# pikahome.net
KiCad netlist of a schematic drawn in EAGLE
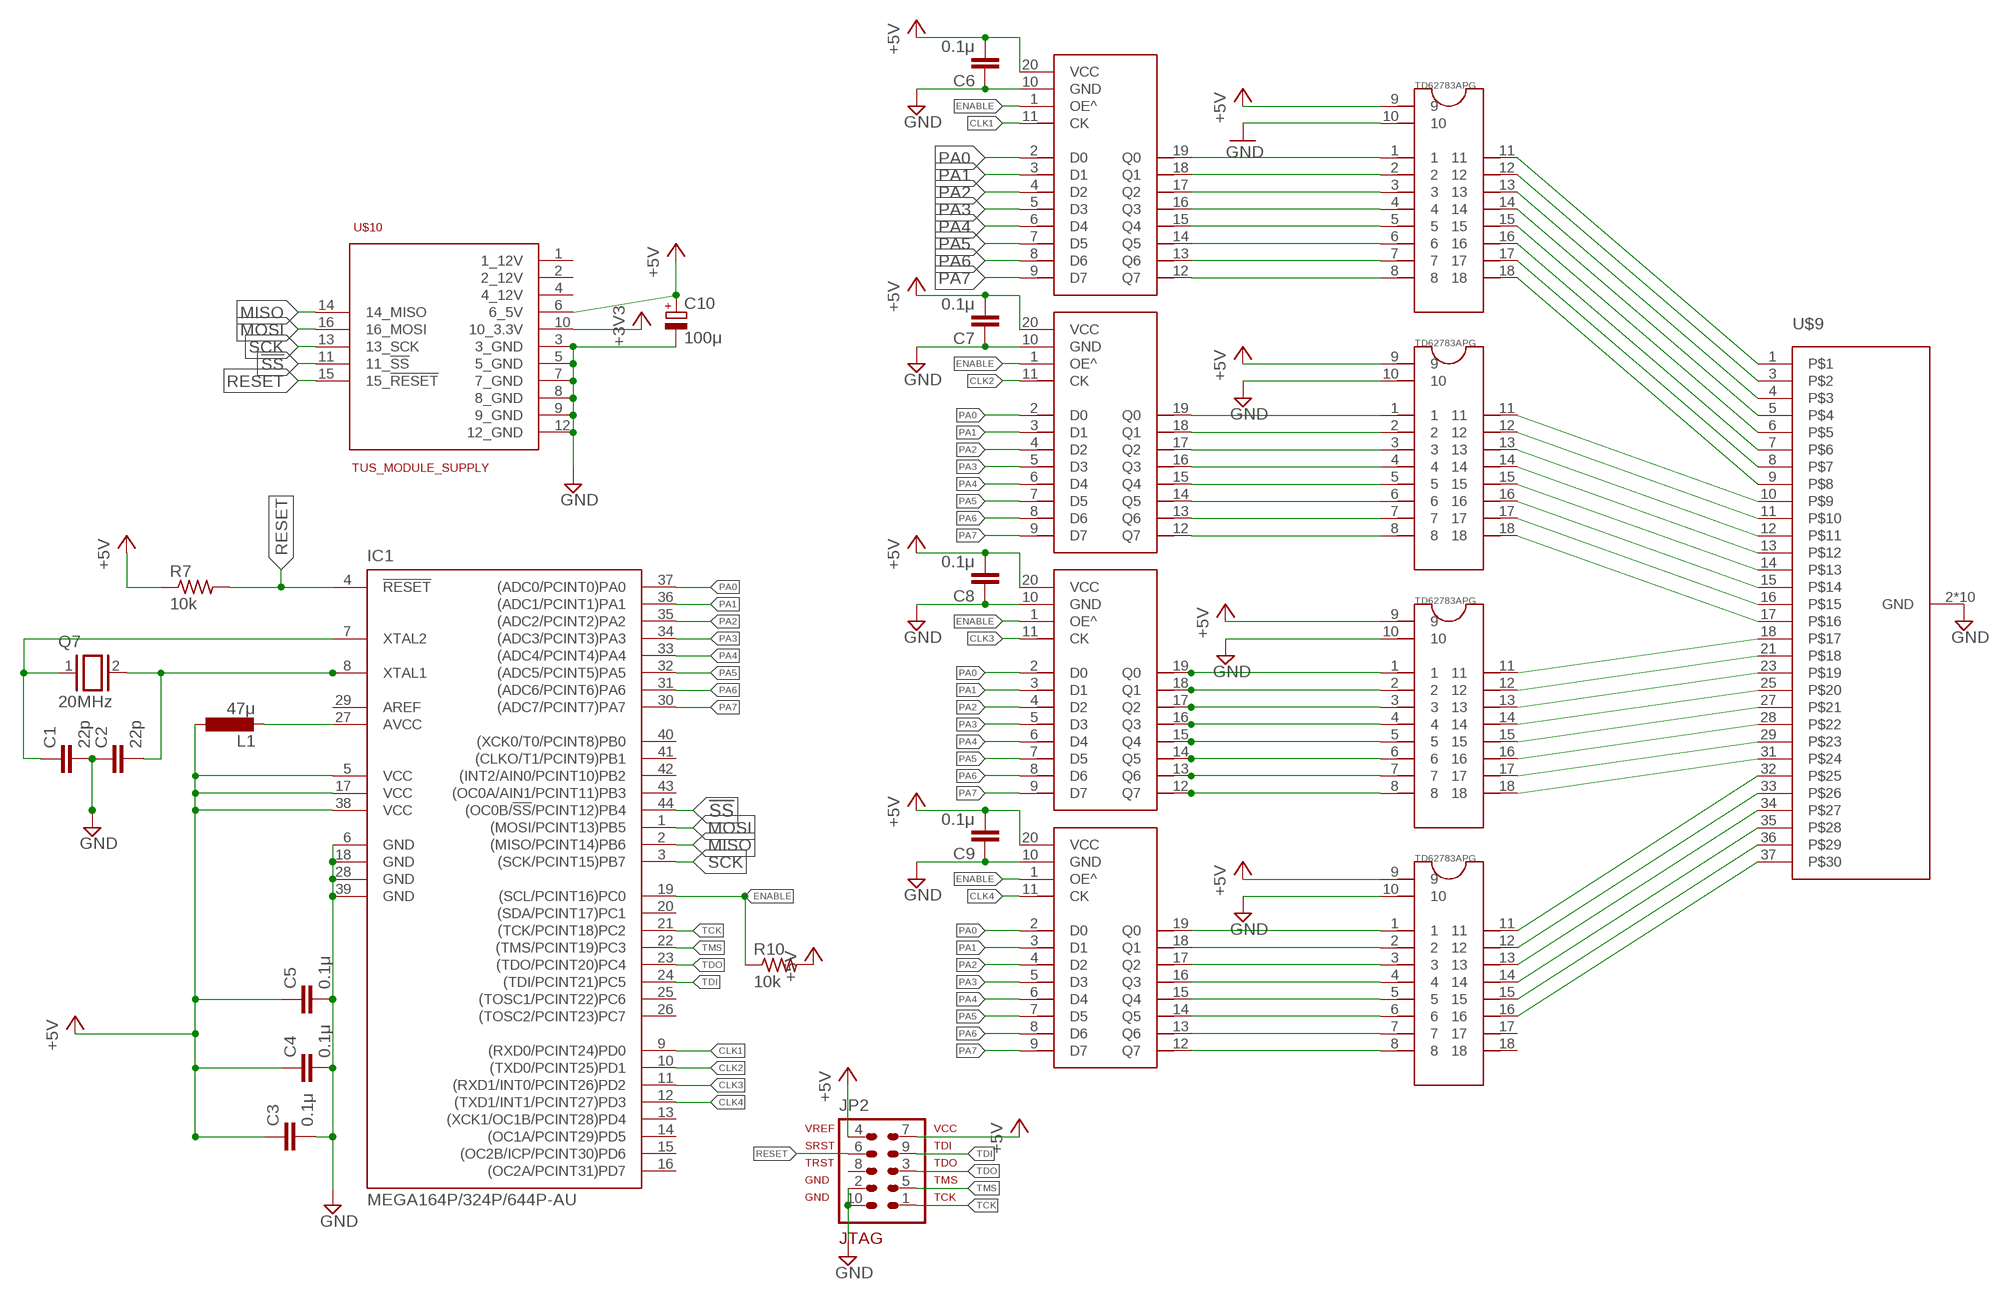
[diagram p0: schematic, sheet 1]

(export (version "E")
  (design (tool "Eeschema 10.0.6"))
  (components
    (comp (ref "C1")
      (value "22p")
      (footprint "eagle-import:C0603")
      (libsource (lib "eagle-import") (part "C-EUC0603"))
    )
    (comp (ref "C2")
      (value "22p")
      (footprint "eagle-import:C0603")
      (libsource (lib "eagle-import") (part "C-EUC0603"))
    )
    (comp (ref "C3")
      (value "0.1μ")
      (footprint "eagle-import:C0603")
      (libsource (lib "eagle-import") (part "C-EUC0603"))
    )
    (comp (ref "C4")
      (value "0.1μ")
      (footprint "eagle-import:C0603")
      (libsource (lib "eagle-import") (part "C-EUC0603"))
    )
    (comp (ref "C5")
      (value "0.1μ")
      (footprint "eagle-import:C0603")
      (libsource (lib "eagle-import") (part "C-EUC0603"))
    )
    (comp (ref "C6")
      (value "0.1μ")
      (footprint "eagle-import:C0603")
      (libsource (lib "eagle-import") (part "C-EUC0603"))
    )
    (comp (ref "C7")
      (value "0.1μ")
      (footprint "eagle-import:C0603")
      (libsource (lib "eagle-import") (part "C-EUC0603"))
    )
    (comp (ref "C8")
      (value "0.1μ")
      (footprint "eagle-import:C0603")
      (libsource (lib "eagle-import") (part "C-EUC0603"))
    )
    (comp (ref "C9")
      (value "0.1μ")
      (footprint "eagle-import:C0603")
      (libsource (lib "eagle-import") (part "C-EUC0603"))
    )
    (comp (ref "C10")
      (value "100μ")
      (footprint "eagle-import:TT2D5")
      (libsource (lib "eagle-import") (part "CPOL-EUTT2D5"))
    )
    (comp (ref "IC1")
      (value "MEGA164P/324P/644P-AU")
      (footprint "eagle-import:TQFP44")
      (libsource (lib "eagle-import") (part "MEGA164P/324P/644P-AU"))
    )
    (comp (ref "JP2")
      (value "AVR-JTAG-10")
      (footprint "eagle-import:AVR-JTAG-10")
      (libsource (lib "eagle-import") (part "AVR-JTAG-10"))
    )
    (comp (ref "L1")
      (value "47μ")
      (footprint "eagle-import:L3216C")
      (libsource (lib "eagle-import") (part "L-EUL3216C"))
    )
    (comp (ref "Q7")
      (value "20MHz")
      (footprint "eagle-import:QS")
      (libsource (lib "eagle-import") (part "XTAL/S"))
    )
    (comp (ref "R7")
      (value "10k")
      (footprint "eagle-import:R0603")
      (libsource (lib "eagle-import") (part "R-US_R0603"))
    )
    (comp (ref "R10")
      (value "10k")
      (footprint "eagle-import:R0603")
      (libsource (lib "eagle-import") (part "R-US_R0603"))
    )
    (comp (ref "U$1")
      (value "TD62783APG")
      (footprint "eagle-import:DIL18")
      (libsource (lib "eagle-import") (part "TD62783APG"))
    )
    (comp (ref "U$2")
      (value "TD62783APG")
      (footprint "eagle-import:DIL18")
      (libsource (lib "eagle-import") (part "TD62783APG"))
    )
    (comp (ref "U$3")
      (value "74VHC574F")
      (footprint "eagle-import:SO20W")
      (libsource (lib "eagle-import") (part "74VHC574F"))
    )
    (comp (ref "U$4")
      (value "74VHC574F")
      (footprint "eagle-import:SO20W")
      (libsource (lib "eagle-import") (part "74VHC574F"))
    )
    (comp (ref "U$5")
      (value "74VHC574F")
      (footprint "eagle-import:SO20W")
      (libsource (lib "eagle-import") (part "74VHC574F"))
    )
    (comp (ref "U$6")
      (value "TD62783APG")
      (footprint "eagle-import:DIL18")
      (libsource (lib "eagle-import") (part "TD62783APG"))
    )
    (comp (ref "U$7")
      (value "74VHC574F")
      (footprint "eagle-import:SO20W")
      (libsource (lib "eagle-import") (part "74VHC574F"))
    )
    (comp (ref "U$8")
      (value "TD62783APG")
      (footprint "eagle-import:DIL18")
      (libsource (lib "eagle-import") (part "TD62783APG"))
    )
    (comp (ref "U$9")
      (value "LED_40")
      (footprint "eagle-import:PAK100_2500-40")
      (libsource (lib "eagle-import") (part "LED_40"))
    )
    (comp (ref "U$10")
      (value "TUS_MODULE_SUPPLY")
      (footprint "eagle-import:2X08")
      (libsource (lib "eagle-import") (part "TUS_MODULE_SUPPLY"))
    )
  )
  (nets
    (net (code "1") (name "+3V3") (class "Default")
      (node (ref "U$10") (pin "10") (pinfunction "10_3.3V_10") (pintype "bidirectional"))
    )
    (net (code "2") (name "+5V") (class "Default")
      (node (ref "C10") (pin "+") (pinfunction "+_+") (pintype "passive"))
      (node (ref "C3") (pin "1") (pinfunction "1_1") (pintype "passive"))
      (node (ref "C4") (pin "1") (pinfunction "1_1") (pintype "passive"))
      (node (ref "C5") (pin "1") (pinfunction "1_1") (pintype "passive"))
      (node (ref "C6") (pin "2") (pinfunction "2_2") (pintype "passive"))
      (node (ref "C7") (pin "2") (pinfunction "2_2") (pintype "passive"))
      (node (ref "C8") (pin "2") (pinfunction "2_2") (pintype "passive"))
      (node (ref "C9") (pin "2") (pinfunction "2_2") (pintype "passive"))
      (node (ref "IC1") (pin "17") (pinfunction "VCC_17") (pintype "power_in"))
      (node (ref "IC1") (pin "38") (pinfunction "VCC_38") (pintype "power_in"))
      (node (ref "IC1") (pin "5") (pinfunction "VCC_5") (pintype "power_in"))
      (node (ref "JP2") (pin "4") (pinfunction "4_4") (pintype "passive"))
      (node (ref "JP2") (pin "7") (pinfunction "7_7") (pintype "passive"))
      (node (ref "L1") (pin "1") (pinfunction "1_1") (pintype "passive"))
      (node (ref "R10") (pin "2") (pinfunction "2_2") (pintype "passive"))
      (node (ref "R7") (pin "1") (pinfunction "1_1") (pintype "passive"))
      (node (ref "U$1") (pin "9") (pinfunction "9_9") (pintype "power_in"))
      (node (ref "U$10") (pin "6") (pinfunction "6_5V_6") (pintype "bidirectional"))
      (node (ref "U$2") (pin "9") (pinfunction "9_9") (pintype "power_in"))
      (node (ref "U$3") (pin "20") (pinfunction "VCC_20") (pintype "bidirectional"))
      (node (ref "U$4") (pin "20") (pinfunction "VCC_20") (pintype "bidirectional"))
      (node (ref "U$5") (pin "20") (pinfunction "VCC_20") (pintype "bidirectional"))
      (node (ref "U$6") (pin "9") (pinfunction "9_9") (pintype "power_in"))
      (node (ref "U$7") (pin "20") (pinfunction "VCC_20") (pintype "bidirectional"))
      (node (ref "U$8") (pin "9") (pinfunction "9_9") (pintype "power_in"))
    )
    (net (code "3") (name "/AREF") (class "Default")
      (node (ref "IC1") (pin "29") (pinfunction "AREF_29") (pintype "power_in"))
    )
    (net (code "4") (name "/~{SS}") (class "Default")
      (node (ref "IC1") (pin "44") (pinfunction "(OC0B/~{SS}/PCINT12)PB4_44") (pintype "bidirectional"))
      (node (ref "U$10") (pin "11") (pinfunction "11_~{SS}_11") (pintype "bidirectional"))
    )
    (net (code "5") (name "CLK1") (class "Default")
      (node (ref "IC1") (pin "9") (pinfunction "(RXD0/PCINT24)PD0_9") (pintype "bidirectional"))
      (node (ref "U$3") (pin "11") (pinfunction "CK_11") (pintype "bidirectional"))
    )
    (net (code "6") (name "CLK2") (class "Default")
      (node (ref "IC1") (pin "10") (pinfunction "(TXD0/PCINT25)PD1_10") (pintype "bidirectional"))
      (node (ref "U$4") (pin "11") (pinfunction "CK_11") (pintype "bidirectional"))
    )
    (net (code "7") (name "CLK3") (class "Default")
      (node (ref "IC1") (pin "11") (pinfunction "(RXD1/INT0/PCINT26)PD2_11") (pintype "bidirectional"))
      (node (ref "U$5") (pin "11") (pinfunction "CK_11") (pintype "bidirectional"))
    )
    (net (code "8") (name "CLK4") (class "Default")
      (node (ref "IC1") (pin "12") (pinfunction "(TXD1/INT1/PCINT27)PD3_12") (pintype "bidirectional"))
      (node (ref "U$7") (pin "11") (pinfunction "CK_11") (pintype "bidirectional"))
    )
    (net (code "9") (name "ENABLE") (class "Default")
      (node (ref "IC1") (pin "19") (pinfunction "(SCL/PCINT16)PC0_19") (pintype "bidirectional"))
      (node (ref "R10") (pin "1") (pinfunction "1_1") (pintype "passive"))
      (node (ref "U$3") (pin "1") (pinfunction "OE^_1") (pintype "bidirectional"))
      (node (ref "U$4") (pin "1") (pinfunction "OE^_1") (pintype "bidirectional"))
      (node (ref "U$5") (pin "1") (pinfunction "OE^_1") (pintype "bidirectional"))
      (node (ref "U$7") (pin "1") (pinfunction "OE^_1") (pintype "bidirectional"))
    )
    (net (code "10") (name "GND") (class "Default")
      (node (ref "C1") (pin "2") (pinfunction "2_2") (pintype "passive"))
      (node (ref "C10") (pin "-") (pinfunction "-_-") (pintype "passive"))
      (node (ref "C2") (pin "1") (pinfunction "1_1") (pintype "passive"))
      (node (ref "C3") (pin "2") (pinfunction "2_2") (pintype "passive"))
      (node (ref "C4") (pin "2") (pinfunction "2_2") (pintype "passive"))
      (node (ref "C5") (pin "2") (pinfunction "2_2") (pintype "passive"))
      (node (ref "C6") (pin "1") (pinfunction "1_1") (pintype "passive"))
      (node (ref "C7") (pin "1") (pinfunction "1_1") (pintype "passive"))
      (node (ref "C8") (pin "1") (pinfunction "1_1") (pintype "passive"))
      (node (ref "C9") (pin "1") (pinfunction "1_1") (pintype "passive"))
      (node (ref "IC1") (pin "18") (pinfunction "GND_18") (pintype "power_in"))
      (node (ref "IC1") (pin "28") (pinfunction "GND_28") (pintype "power_in"))
      (node (ref "IC1") (pin "39") (pinfunction "GND_39") (pintype "power_in"))
      (node (ref "IC1") (pin "6") (pinfunction "GND_6") (pintype "power_in"))
      (node (ref "JP2") (pin "10") (pinfunction "10_10") (pintype "passive"))
      (node (ref "JP2") (pin "2") (pinfunction "2_2") (pintype "passive"))
      (node (ref "U$1") (pin "10") (pinfunction "10_10") (pintype "power_in"))
      (node (ref "U$10") (pin "12") (pinfunction "12_GND_12") (pintype "bidirectional"))
      (node (ref "U$10") (pin "3") (pinfunction "3_GND_3") (pintype "bidirectional"))
      (node (ref "U$10") (pin "5") (pinfunction "5_GND_5") (pintype "bidirectional"))
      (node (ref "U$10") (pin "7") (pinfunction "7_GND_7") (pintype "bidirectional"))
      (node (ref "U$10") (pin "8") (pinfunction "8_GND_8") (pintype "bidirectional"))
      (node (ref "U$10") (pin "9") (pinfunction "9_GND_9") (pintype "bidirectional"))
      (node (ref "U$2") (pin "10") (pinfunction "10_10") (pintype "power_in"))
      (node (ref "U$3") (pin "10") (pinfunction "GND_10") (pintype "bidirectional"))
      (node (ref "U$4") (pin "10") (pinfunction "GND_10") (pintype "bidirectional"))
      (node (ref "U$5") (pin "10") (pinfunction "GND_10") (pintype "bidirectional"))
      (node (ref "U$6") (pin "10") (pinfunction "10_10") (pintype "power_in"))
      (node (ref "U$7") (pin "10") (pinfunction "GND_10") (pintype "bidirectional"))
      (node (ref "U$8") (pin "10") (pinfunction "10_10") (pintype "power_in"))
      (node (ref "U$9") (pin "19") (pinfunction "GND_19") (pintype "bidirectional"))
      (node (ref "U$9") (pin "2") (pinfunction "GND_2") (pintype "bidirectional"))
      (node (ref "U$9") (pin "20") (pinfunction "GND_20") (pintype "bidirectional"))
      (node (ref "U$9") (pin "22") (pinfunction "GND_22") (pintype "bidirectional"))
      (node (ref "U$9") (pin "24") (pinfunction "GND_24") (pintype "bidirectional"))
      (node (ref "U$9") (pin "26") (pinfunction "GND_26") (pintype "bidirectional"))
      (node (ref "U$9") (pin "30") (pinfunction "GND_30") (pintype "bidirectional"))
      (node (ref "U$9") (pin "38") (pinfunction "GND_38") (pintype "bidirectional"))
      (node (ref "U$9") (pin "39") (pinfunction "GND_39") (pintype "bidirectional"))
      (node (ref "U$9") (pin "40") (pinfunction "GND_40") (pintype "bidirectional"))
    )
    (net (code "11") (name "MISO") (class "Default")
      (node (ref "IC1") (pin "2") (pinfunction "(MISO/PCINT14)PB6_2") (pintype "bidirectional"))
      (node (ref "U$10") (pin "14") (pinfunction "14_MISO_14") (pintype "bidirectional"))
    )
    (net (code "12") (name "MOSI") (class "Default")
      (node (ref "IC1") (pin "1") (pinfunction "(MOSI/PCINT13)PB5_1") (pintype "bidirectional"))
      (node (ref "U$10") (pin "16") (pinfunction "16_MOSI_16") (pintype "bidirectional"))
    )
    (net (code "13") (name "Net-(IC1-AVCC)") (class "Default")
      (node (ref "IC1") (pin "27") (pinfunction "AVCC_27") (pintype "power_in"))
      (node (ref "L1") (pin "2") (pinfunction "2_2") (pintype "passive"))
    )
    (net (code "14") (name "Net-(IC1-XTAL1)") (class "Default")
      (node (ref "C2") (pin "2") (pinfunction "2_2") (pintype "passive"))
      (node (ref "IC1") (pin "8") (pinfunction "XTAL1_8") (pintype "input"))
      (node (ref "Q7") (pin "2") (pinfunction "2_2") (pintype "passive"))
    )
    (net (code "15") (name "Net-(IC1-XTAL2)") (class "Default")
      (node (ref "C1") (pin "1") (pinfunction "1_1") (pintype "passive"))
      (node (ref "IC1") (pin "7") (pinfunction "XTAL2_7") (pintype "output"))
      (node (ref "Q7") (pin "1") (pinfunction "1_1") (pintype "passive"))
    )
    (net (code "16") (name "Net-(U$3-Q0)") (class "Default")
      (node (ref "U$1") (pin "1") (pinfunction "1_1") (pintype "input"))
      (node (ref "U$3") (pin "19") (pinfunction "Q0_19") (pintype "bidirectional"))
    )
    (net (code "17") (name "Net-(U$3-Q1)") (class "Default")
      (node (ref "U$1") (pin "2") (pinfunction "2_2") (pintype "input"))
      (node (ref "U$3") (pin "18") (pinfunction "Q1_18") (pintype "bidirectional"))
    )
    (net (code "18") (name "Net-(U$3-Q2)") (class "Default")
      (node (ref "U$1") (pin "3") (pinfunction "3_3") (pintype "input"))
      (node (ref "U$3") (pin "17") (pinfunction "Q2_17") (pintype "bidirectional"))
    )
    (net (code "19") (name "Net-(U$3-Q3)") (class "Default")
      (node (ref "U$1") (pin "4") (pinfunction "4_4") (pintype "input"))
      (node (ref "U$3") (pin "16") (pinfunction "Q3_16") (pintype "bidirectional"))
    )
    (net (code "20") (name "Net-(U$3-Q4)") (class "Default")
      (node (ref "U$1") (pin "5") (pinfunction "5_5") (pintype "input"))
      (node (ref "U$3") (pin "15") (pinfunction "Q4_15") (pintype "bidirectional"))
    )
    (net (code "21") (name "Net-(U$3-Q5)") (class "Default")
      (node (ref "U$1") (pin "6") (pinfunction "6_6") (pintype "input"))
      (node (ref "U$3") (pin "14") (pinfunction "Q5_14") (pintype "bidirectional"))
    )
    (net (code "22") (name "Net-(U$3-Q6)") (class "Default")
      (node (ref "U$1") (pin "7") (pinfunction "7_7") (pintype "input"))
      (node (ref "U$3") (pin "13") (pinfunction "Q6_13") (pintype "bidirectional"))
    )
    (net (code "23") (name "Net-(U$3-Q7)") (class "Default")
      (node (ref "U$1") (pin "8") (pinfunction "8_8") (pintype "input"))
      (node (ref "U$3") (pin "12") (pinfunction "Q7_12") (pintype "bidirectional"))
    )
    (net (code "24") (name "Net-(U$4-Q0)") (class "Default")
      (node (ref "U$2") (pin "1") (pinfunction "1_1") (pintype "input"))
      (node (ref "U$4") (pin "19") (pinfunction "Q0_19") (pintype "bidirectional"))
    )
    (net (code "25") (name "Net-(U$4-Q1)") (class "Default")
      (node (ref "U$2") (pin "2") (pinfunction "2_2") (pintype "input"))
      (node (ref "U$4") (pin "18") (pinfunction "Q1_18") (pintype "bidirectional"))
    )
    (net (code "26") (name "Net-(U$4-Q2)") (class "Default")
      (node (ref "U$2") (pin "3") (pinfunction "3_3") (pintype "input"))
      (node (ref "U$4") (pin "17") (pinfunction "Q2_17") (pintype "bidirectional"))
    )
    (net (code "27") (name "Net-(U$4-Q3)") (class "Default")
      (node (ref "U$2") (pin "4") (pinfunction "4_4") (pintype "input"))
      (node (ref "U$4") (pin "16") (pinfunction "Q3_16") (pintype "bidirectional"))
    )
    (net (code "28") (name "Net-(U$4-Q4)") (class "Default")
      (node (ref "U$2") (pin "5") (pinfunction "5_5") (pintype "input"))
      (node (ref "U$4") (pin "15") (pinfunction "Q4_15") (pintype "bidirectional"))
    )
    (net (code "29") (name "Net-(U$4-Q5)") (class "Default")
      (node (ref "U$2") (pin "6") (pinfunction "6_6") (pintype "input"))
      (node (ref "U$4") (pin "14") (pinfunction "Q5_14") (pintype "bidirectional"))
    )
    (net (code "30") (name "Net-(U$4-Q6)") (class "Default")
      (node (ref "U$2") (pin "7") (pinfunction "7_7") (pintype "input"))
      (node (ref "U$4") (pin "13") (pinfunction "Q6_13") (pintype "bidirectional"))
    )
    (net (code "31") (name "Net-(U$4-Q7)") (class "Default")
      (node (ref "U$2") (pin "8") (pinfunction "8_8") (pintype "input"))
      (node (ref "U$4") (pin "12") (pinfunction "Q7_12") (pintype "bidirectional"))
    )
    (net (code "32") (name "Net-(U$5-Q0)") (class "Default")
      (node (ref "U$5") (pin "19") (pinfunction "Q0_19") (pintype "bidirectional"))
      (node (ref "U$6") (pin "1") (pinfunction "1_1") (pintype "input"))
    )
    (net (code "33") (name "Net-(U$5-Q1)") (class "Default")
      (node (ref "U$5") (pin "18") (pinfunction "Q1_18") (pintype "bidirectional"))
      (node (ref "U$6") (pin "2") (pinfunction "2_2") (pintype "input"))
    )
    (net (code "34") (name "Net-(U$5-Q2)") (class "Default")
      (node (ref "U$5") (pin "17") (pinfunction "Q2_17") (pintype "bidirectional"))
      (node (ref "U$6") (pin "3") (pinfunction "3_3") (pintype "input"))
    )
    (net (code "35") (name "Net-(U$5-Q3)") (class "Default")
      (node (ref "U$5") (pin "16") (pinfunction "Q3_16") (pintype "bidirectional"))
      (node (ref "U$6") (pin "4") (pinfunction "4_4") (pintype "input"))
    )
    (net (code "36") (name "Net-(U$5-Q4)") (class "Default")
      (node (ref "U$5") (pin "15") (pinfunction "Q4_15") (pintype "bidirectional"))
      (node (ref "U$6") (pin "5") (pinfunction "5_5") (pintype "input"))
    )
    (net (code "37") (name "Net-(U$5-Q5)") (class "Default")
      (node (ref "U$5") (pin "14") (pinfunction "Q5_14") (pintype "bidirectional"))
      (node (ref "U$6") (pin "6") (pinfunction "6_6") (pintype "input"))
    )
    (net (code "38") (name "Net-(U$5-Q6)") (class "Default")
      (node (ref "U$5") (pin "13") (pinfunction "Q6_13") (pintype "bidirectional"))
      (node (ref "U$6") (pin "7") (pinfunction "7_7") (pintype "input"))
    )
    (net (code "39") (name "Net-(U$5-Q7)") (class "Default")
      (node (ref "U$5") (pin "12") (pinfunction "Q7_12") (pintype "bidirectional"))
      (node (ref "U$6") (pin "8") (pinfunction "8_8") (pintype "input"))
    )
    (net (code "40") (name "Net-(U$7-Q0)") (class "Default")
      (node (ref "U$7") (pin "19") (pinfunction "Q0_19") (pintype "bidirectional"))
      (node (ref "U$8") (pin "1") (pinfunction "1_1") (pintype "input"))
    )
    (net (code "41") (name "Net-(U$7-Q1)") (class "Default")
      (node (ref "U$7") (pin "18") (pinfunction "Q1_18") (pintype "bidirectional"))
      (node (ref "U$8") (pin "2") (pinfunction "2_2") (pintype "input"))
    )
    (net (code "42") (name "Net-(U$7-Q2)") (class "Default")
      (node (ref "U$7") (pin "17") (pinfunction "Q2_17") (pintype "bidirectional"))
      (node (ref "U$8") (pin "3") (pinfunction "3_3") (pintype "input"))
    )
    (net (code "43") (name "Net-(U$7-Q3)") (class "Default")
      (node (ref "U$7") (pin "16") (pinfunction "Q3_16") (pintype "bidirectional"))
      (node (ref "U$8") (pin "4") (pinfunction "4_4") (pintype "input"))
    )
    (net (code "44") (name "Net-(U$7-Q4)") (class "Default")
      (node (ref "U$7") (pin "15") (pinfunction "Q4_15") (pintype "bidirectional"))
      (node (ref "U$8") (pin "5") (pinfunction "5_5") (pintype "input"))
    )
    (net (code "45") (name "Net-(U$7-Q5)") (class "Default")
      (node (ref "U$7") (pin "14") (pinfunction "Q5_14") (pintype "bidirectional"))
      (node (ref "U$8") (pin "6") (pinfunction "6_6") (pintype "input"))
    )
    (net (code "46") (name "Net-(U$7-Q6)") (class "Default")
      (node (ref "U$7") (pin "13") (pinfunction "Q6_13") (pintype "bidirectional"))
      (node (ref "U$8") (pin "7") (pinfunction "7_7") (pintype "input"))
    )
    (net (code "47") (name "Net-(U$7-Q7)") (class "Default")
      (node (ref "U$7") (pin "12") (pinfunction "Q7_12") (pintype "bidirectional"))
      (node (ref "U$8") (pin "8") (pinfunction "8_8") (pintype "input"))
    )
    (net (code "48") (name "Net-(U$9-P$1)") (class "Default")
      (node (ref "U$1") (pin "11") (pinfunction "11_11") (pintype "output"))
      (node (ref "U$9") (pin "1") (pinfunction "P$1_1") (pintype "bidirectional"))
    )
    (net (code "49") (name "Net-(U$9-P$2)") (class "Default")
      (node (ref "U$1") (pin "12") (pinfunction "12_12") (pintype "output"))
      (node (ref "U$9") (pin "3") (pinfunction "P$2_3") (pintype "bidirectional"))
    )
    (net (code "50") (name "Net-(U$9-P$3)") (class "Default")
      (node (ref "U$1") (pin "13") (pinfunction "13_13") (pintype "output"))
      (node (ref "U$9") (pin "4") (pinfunction "P$3_4") (pintype "bidirectional"))
    )
    (net (code "51") (name "Net-(U$9-P$4)") (class "Default")
      (node (ref "U$1") (pin "14") (pinfunction "14_14") (pintype "output"))
      (node (ref "U$9") (pin "5") (pinfunction "P$4_5") (pintype "bidirectional"))
    )
    (net (code "52") (name "Net-(U$9-P$5)") (class "Default")
      (node (ref "U$1") (pin "15") (pinfunction "15_15") (pintype "output"))
      (node (ref "U$9") (pin "6") (pinfunction "P$5_6") (pintype "bidirectional"))
    )
    (net (code "53") (name "Net-(U$9-P$6)") (class "Default")
      (node (ref "U$1") (pin "16") (pinfunction "16_16") (pintype "output"))
      (node (ref "U$9") (pin "7") (pinfunction "P$6_7") (pintype "bidirectional"))
    )
    (net (code "54") (name "Net-(U$9-P$7)") (class "Default")
      (node (ref "U$1") (pin "17") (pinfunction "17_17") (pintype "output"))
      (node (ref "U$9") (pin "8") (pinfunction "P$7_8") (pintype "bidirectional"))
    )
    (net (code "55") (name "Net-(U$9-P$8)") (class "Default")
      (node (ref "U$1") (pin "18") (pinfunction "18_18") (pintype "output"))
      (node (ref "U$9") (pin "9") (pinfunction "P$8_9") (pintype "bidirectional"))
    )
    (net (code "56") (name "Net-(U$9-P$9)") (class "Default")
      (node (ref "U$2") (pin "11") (pinfunction "11_11") (pintype "output"))
      (node (ref "U$9") (pin "10") (pinfunction "P$9_10") (pintype "bidirectional"))
    )
    (net (code "57") (name "Net-(U$9-P$10)") (class "Default")
      (node (ref "U$2") (pin "12") (pinfunction "12_12") (pintype "output"))
      (node (ref "U$9") (pin "11") (pinfunction "P$10_11") (pintype "bidirectional"))
    )
    (net (code "58") (name "Net-(U$9-P$11)") (class "Default")
      (node (ref "U$2") (pin "13") (pinfunction "13_13") (pintype "output"))
      (node (ref "U$9") (pin "12") (pinfunction "P$11_12") (pintype "bidirectional"))
    )
    (net (code "59") (name "Net-(U$9-P$12)") (class "Default")
      (node (ref "U$2") (pin "14") (pinfunction "14_14") (pintype "output"))
      (node (ref "U$9") (pin "13") (pinfunction "P$12_13") (pintype "bidirectional"))
    )
    (net (code "60") (name "Net-(U$9-P$13)") (class "Default")
      (node (ref "U$2") (pin "15") (pinfunction "15_15") (pintype "output"))
      (node (ref "U$9") (pin "14") (pinfunction "P$13_14") (pintype "bidirectional"))
    )
    (net (code "61") (name "Net-(U$9-P$14)") (class "Default")
      (node (ref "U$2") (pin "16") (pinfunction "16_16") (pintype "output"))
      (node (ref "U$9") (pin "15") (pinfunction "P$14_15") (pintype "bidirectional"))
    )
    (net (code "62") (name "Net-(U$9-P$15)") (class "Default")
      (node (ref "U$2") (pin "17") (pinfunction "17_17") (pintype "output"))
      (node (ref "U$9") (pin "16") (pinfunction "P$15_16") (pintype "bidirectional"))
    )
    (net (code "63") (name "Net-(U$9-P$16)") (class "Default")
      (node (ref "U$2") (pin "18") (pinfunction "18_18") (pintype "output"))
      (node (ref "U$9") (pin "17") (pinfunction "P$16_17") (pintype "bidirectional"))
    )
    (net (code "64") (name "Net-(U$9-P$17)") (class "Default")
      (node (ref "U$6") (pin "11") (pinfunction "11_11") (pintype "output"))
      (node (ref "U$9") (pin "18") (pinfunction "P$17_18") (pintype "bidirectional"))
    )
    (net (code "65") (name "Net-(U$9-P$18)") (class "Default")
      (node (ref "U$6") (pin "12") (pinfunction "12_12") (pintype "output"))
      (node (ref "U$9") (pin "21") (pinfunction "P$18_21") (pintype "bidirectional"))
    )
    (net (code "66") (name "Net-(U$9-P$19)") (class "Default")
      (node (ref "U$6") (pin "13") (pinfunction "13_13") (pintype "output"))
      (node (ref "U$9") (pin "23") (pinfunction "P$19_23") (pintype "bidirectional"))
    )
    (net (code "67") (name "Net-(U$9-P$20)") (class "Default")
      (node (ref "U$6") (pin "14") (pinfunction "14_14") (pintype "output"))
      (node (ref "U$9") (pin "25") (pinfunction "P$20_25") (pintype "bidirectional"))
    )
    (net (code "68") (name "Net-(U$9-P$21)") (class "Default")
      (node (ref "U$6") (pin "15") (pinfunction "15_15") (pintype "output"))
      (node (ref "U$9") (pin "27") (pinfunction "P$21_27") (pintype "bidirectional"))
    )
    (net (code "69") (name "Net-(U$9-P$22)") (class "Default")
      (node (ref "U$6") (pin "16") (pinfunction "16_16") (pintype "output"))
      (node (ref "U$9") (pin "28") (pinfunction "P$22_28") (pintype "bidirectional"))
    )
    (net (code "70") (name "Net-(U$9-P$23)") (class "Default")
      (node (ref "U$6") (pin "17") (pinfunction "17_17") (pintype "output"))
      (node (ref "U$9") (pin "29") (pinfunction "P$23_29") (pintype "bidirectional"))
    )
    (net (code "71") (name "Net-(U$9-P$24)") (class "Default")
      (node (ref "U$6") (pin "18") (pinfunction "18_18") (pintype "output"))
      (node (ref "U$9") (pin "31") (pinfunction "P$24_31") (pintype "bidirectional"))
    )
    (net (code "72") (name "Net-(U$9-P$25)") (class "Default")
      (node (ref "U$8") (pin "11") (pinfunction "11_11") (pintype "output"))
      (node (ref "U$9") (pin "32") (pinfunction "P$25_32") (pintype "bidirectional"))
    )
    (net (code "73") (name "Net-(U$9-P$26)") (class "Default")
      (node (ref "U$8") (pin "12") (pinfunction "12_12") (pintype "output"))
      (node (ref "U$9") (pin "33") (pinfunction "P$26_33") (pintype "bidirectional"))
    )
    (net (code "74") (name "Net-(U$9-P$27)") (class "Default")
      (node (ref "U$8") (pin "13") (pinfunction "13_13") (pintype "output"))
      (node (ref "U$9") (pin "34") (pinfunction "P$27_34") (pintype "bidirectional"))
    )
    (net (code "75") (name "Net-(U$9-P$28)") (class "Default")
      (node (ref "U$8") (pin "14") (pinfunction "14_14") (pintype "output"))
      (node (ref "U$9") (pin "35") (pinfunction "P$28_35") (pintype "bidirectional"))
    )
    (net (code "76") (name "Net-(U$9-P$29)") (class "Default")
      (node (ref "U$8") (pin "15") (pinfunction "15_15") (pintype "output"))
      (node (ref "U$9") (pin "36") (pinfunction "P$29_36") (pintype "bidirectional"))
    )
    (net (code "77") (name "Net-(U$9-P$30)") (class "Default")
      (node (ref "U$8") (pin "16") (pinfunction "16_16") (pintype "output"))
      (node (ref "U$9") (pin "37") (pinfunction "P$30_37") (pintype "bidirectional"))
    )
    (net (code "78") (name "PA0") (class "Default")
      (node (ref "IC1") (pin "37") (pinfunction "(ADC0/PCINT0)PA0_37") (pintype "bidirectional"))
      (node (ref "U$3") (pin "2") (pinfunction "D0_2") (pintype "bidirectional"))
      (node (ref "U$4") (pin "2") (pinfunction "D0_2") (pintype "bidirectional"))
      (node (ref "U$5") (pin "2") (pinfunction "D0_2") (pintype "bidirectional"))
      (node (ref "U$7") (pin "2") (pinfunction "D0_2") (pintype "bidirectional"))
    )
    (net (code "79") (name "PA1") (class "Default")
      (node (ref "IC1") (pin "36") (pinfunction "(ADC1/PCINT1)PA1_36") (pintype "bidirectional"))
      (node (ref "U$3") (pin "3") (pinfunction "D1_3") (pintype "bidirectional"))
      (node (ref "U$4") (pin "3") (pinfunction "D1_3") (pintype "bidirectional"))
      (node (ref "U$5") (pin "3") (pinfunction "D1_3") (pintype "bidirectional"))
      (node (ref "U$7") (pin "3") (pinfunction "D1_3") (pintype "bidirectional"))
    )
    (net (code "80") (name "PA2") (class "Default")
      (node (ref "IC1") (pin "35") (pinfunction "(ADC2/PCINT2)PA2_35") (pintype "bidirectional"))
      (node (ref "U$3") (pin "4") (pinfunction "D2_4") (pintype "bidirectional"))
      (node (ref "U$4") (pin "4") (pinfunction "D2_4") (pintype "bidirectional"))
      (node (ref "U$5") (pin "4") (pinfunction "D2_4") (pintype "bidirectional"))
      (node (ref "U$7") (pin "4") (pinfunction "D2_4") (pintype "bidirectional"))
    )
    (net (code "81") (name "PA3") (class "Default")
      (node (ref "IC1") (pin "34") (pinfunction "(ADC3/PCINT3)PA3_34") (pintype "bidirectional"))
      (node (ref "U$3") (pin "5") (pinfunction "D3_5") (pintype "bidirectional"))
      (node (ref "U$4") (pin "5") (pinfunction "D3_5") (pintype "bidirectional"))
      (node (ref "U$5") (pin "5") (pinfunction "D3_5") (pintype "bidirectional"))
      (node (ref "U$7") (pin "5") (pinfunction "D3_5") (pintype "bidirectional"))
    )
    (net (code "82") (name "PA4") (class "Default")
      (node (ref "IC1") (pin "33") (pinfunction "(ADC4/PCINT4)PA4_33") (pintype "bidirectional"))
      (node (ref "U$3") (pin "6") (pinfunction "D4_6") (pintype "bidirectional"))
      (node (ref "U$4") (pin "6") (pinfunction "D4_6") (pintype "bidirectional"))
      (node (ref "U$5") (pin "6") (pinfunction "D4_6") (pintype "bidirectional"))
      (node (ref "U$7") (pin "6") (pinfunction "D4_6") (pintype "bidirectional"))
    )
    (net (code "83") (name "PA5") (class "Default")
      (node (ref "IC1") (pin "32") (pinfunction "(ADC5/PCINT5)PA5_32") (pintype "bidirectional"))
      (node (ref "U$3") (pin "7") (pinfunction "D5_7") (pintype "bidirectional"))
      (node (ref "U$4") (pin "7") (pinfunction "D5_7") (pintype "bidirectional"))
      (node (ref "U$5") (pin "7") (pinfunction "D5_7") (pintype "bidirectional"))
      (node (ref "U$7") (pin "7") (pinfunction "D5_7") (pintype "bidirectional"))
    )
    (net (code "84") (name "PA6") (class "Default")
      (node (ref "IC1") (pin "31") (pinfunction "(ADC6/PCINT6)PA6_31") (pintype "bidirectional"))
      (node (ref "U$3") (pin "8") (pinfunction "D6_8") (pintype "bidirectional"))
      (node (ref "U$4") (pin "8") (pinfunction "D6_8") (pintype "bidirectional"))
      (node (ref "U$5") (pin "8") (pinfunction "D6_8") (pintype "bidirectional"))
      (node (ref "U$7") (pin "8") (pinfunction "D6_8") (pintype "bidirectional"))
    )
    (net (code "85") (name "PA7") (class "Default")
      (node (ref "IC1") (pin "30") (pinfunction "(ADC7/PCINT7)PA7_30") (pintype "bidirectional"))
      (node (ref "U$3") (pin "9") (pinfunction "D7_9") (pintype "bidirectional"))
      (node (ref "U$4") (pin "9") (pinfunction "D7_9") (pintype "bidirectional"))
      (node (ref "U$5") (pin "9") (pinfunction "D7_9") (pintype "bidirectional"))
      (node (ref "U$7") (pin "9") (pinfunction "D7_9") (pintype "bidirectional"))
    )
    (net (code "86") (name "RESET") (class "Default")
      (node (ref "IC1") (pin "4") (pinfunction "~{RESET}_4") (pintype "input"))
      (node (ref "JP2") (pin "6") (pinfunction "6_6") (pintype "passive"))
      (node (ref "R7") (pin "2") (pinfunction "2_2") (pintype "passive"))
      (node (ref "U$10") (pin "15") (pinfunction "15_~{RESET}_15") (pintype "bidirectional"))
    )
    (net (code "87") (name "SCK") (class "Default")
      (node (ref "IC1") (pin "3") (pinfunction "(SCK/PCINT15)PB7_3") (pintype "bidirectional"))
      (node (ref "U$10") (pin "13") (pinfunction "13_SCK_13") (pintype "bidirectional"))
    )
    (net (code "88") (name "TCK") (class "Default")
      (node (ref "IC1") (pin "21") (pinfunction "(TCK/PCINT18)PC2_21") (pintype "bidirectional"))
      (node (ref "JP2") (pin "1") (pinfunction "1_1") (pintype "passive"))
    )
    (net (code "89") (name "TDI") (class "Default")
      (node (ref "IC1") (pin "24") (pinfunction "(TDI/PCINT21)PC5_24") (pintype "bidirectional"))
      (node (ref "JP2") (pin "9") (pinfunction "9_9") (pintype "passive"))
    )
    (net (code "90") (name "TDO") (class "Default")
      (node (ref "IC1") (pin "23") (pinfunction "(TDO/PCINT20)PC4_23") (pintype "bidirectional"))
      (node (ref "JP2") (pin "3") (pinfunction "3_3") (pintype "passive"))
    )
    (net (code "91") (name "TMS") (class "Default")
      (node (ref "IC1") (pin "22") (pinfunction "(TMS/PCINT19)PC3_22") (pintype "bidirectional"))
      (node (ref "JP2") (pin "5") (pinfunction "5_5") (pintype "passive"))
    )
    (net (code "92") (name "unconnected-(IC1-(CLKO{slash}T1{slash}PCINT9)PB1-Pad41)") (class "Default")
      (node (ref "IC1") (pin "41") (pinfunction "(CLKO/T1/PCINT9)PB1_41") (pintype "bidirectional"))
    )
    (net (code "93") (name "unconnected-(IC1-(INT2{slash}AIN0{slash}PCINT10)PB2-Pad42)") (class "Default")
      (node (ref "IC1") (pin "42") (pinfunction "(INT2/AIN0/PCINT10)PB2_42") (pintype "bidirectional"))
    )
    (net (code "94") (name "unconnected-(IC1-(OC0A{slash}AIN1{slash}PCINT11)PB3-Pad43)") (class "Default")
      (node (ref "IC1") (pin "43") (pinfunction "(OC0A/AIN1/PCINT11)PB3_43") (pintype "bidirectional"))
    )
    (net (code "95") (name "unconnected-(IC1-(OC1A{slash}PCINT29)PD5-Pad14)") (class "Default")
      (node (ref "IC1") (pin "14") (pinfunction "(OC1A/PCINT29)PD5_14") (pintype "bidirectional"))
    )
    (net (code "96") (name "unconnected-(IC1-(OC2A{slash}PCINT31)PD7-Pad16)") (class "Default")
      (node (ref "IC1") (pin "16") (pinfunction "(OC2A/PCINT31)PD7_16") (pintype "bidirectional"))
    )
    (net (code "97") (name "unconnected-(IC1-(OC2B{slash}ICP{slash}PCINT30)PD6-Pad15)") (class "Default")
      (node (ref "IC1") (pin "15") (pinfunction "(OC2B/ICP/PCINT30)PD6_15") (pintype "bidirectional"))
    )
    (net (code "98") (name "unconnected-(IC1-(SDA{slash}PCINT17)PC1-Pad20)") (class "Default")
      (node (ref "IC1") (pin "20") (pinfunction "(SDA/PCINT17)PC1_20") (pintype "bidirectional"))
    )
    (net (code "99") (name "unconnected-(IC1-(TOSC1{slash}PCINT22)PC6-Pad25)") (class "Default")
      (node (ref "IC1") (pin "25") (pinfunction "(TOSC1/PCINT22)PC6_25") (pintype "bidirectional"))
    )
    (net (code "100") (name "unconnected-(IC1-(TOSC2{slash}PCINT23)PC7-Pad26)") (class "Default")
      (node (ref "IC1") (pin "26") (pinfunction "(TOSC2/PCINT23)PC7_26") (pintype "bidirectional"))
    )
    (net (code "101") (name "unconnected-(IC1-(XCK0{slash}T0{slash}PCINT8)PB0-Pad40)") (class "Default")
      (node (ref "IC1") (pin "40") (pinfunction "(XCK0/T0/PCINT8)PB0_40") (pintype "bidirectional"))
    )
    (net (code "102") (name "unconnected-(IC1-(XCK1{slash}OC1B{slash}PCINT28)PD4-Pad13)") (class "Default")
      (node (ref "IC1") (pin "13") (pinfunction "(XCK1/OC1B/PCINT28)PD4_13") (pintype "bidirectional"))
    )
    (net (code "103") (name "unconnected-(JP2-Pad8)") (class "Default")
      (node (ref "JP2") (pin "8") (pinfunction "8_8") (pintype "passive"))
    )
    (net (code "104") (name "unconnected-(U$8-Pad17)") (class "Default")
      (node (ref "U$8") (pin "17") (pinfunction "17_17") (pintype "output"))
    )
    (net (code "105") (name "unconnected-(U$8-Pad18)") (class "Default")
      (node (ref "U$8") (pin "18") (pinfunction "18_18") (pintype "output"))
    )
    (net (code "106") (name "unconnected-(U$10-1_12V-Pad1)") (class "Default")
      (node (ref "U$10") (pin "1") (pinfunction "1_12V_1") (pintype "bidirectional"))
    )
    (net (code "107") (name "unconnected-(U$10-2_12V-Pad2)") (class "Default")
      (node (ref "U$10") (pin "2") (pinfunction "2_12V_2") (pintype "bidirectional"))
    )
    (net (code "108") (name "unconnected-(U$10-4_12V-Pad4)") (class "Default")
      (node (ref "U$10") (pin "4") (pinfunction "4_12V_4") (pintype "bidirectional"))
    )
  )
)
